# jetson_board.net
KiCad netlist of a schematic drawn in EAGLE
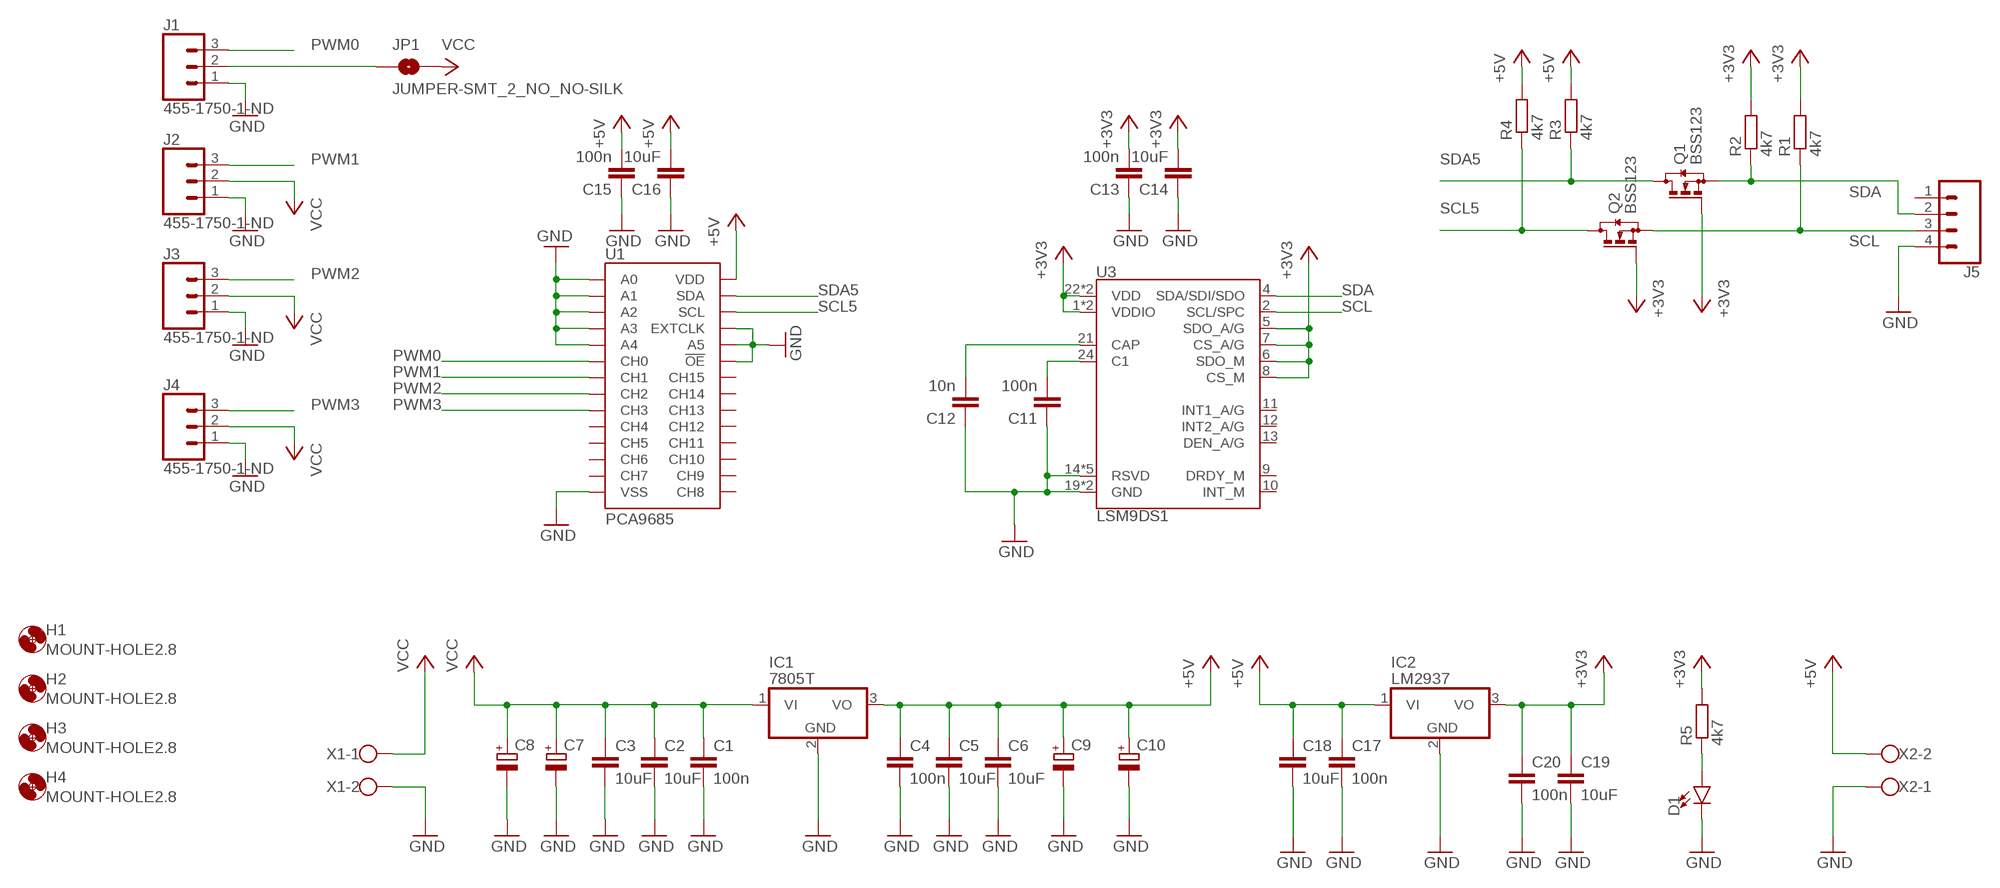
[diagram p0: schematic, sheet 1]

(export (version "E")
  (design (tool "Eeschema 10.0.6"))
  (components
    (comp (ref "C1")
      (value "100n")
      (footprint "eagle-import:C0805")
      (libsource (lib "eagle-import") (part "C-EUC0805"))
    )
    (comp (ref "C2")
      (value "10uF")
      (footprint "eagle-import:C0805")
      (libsource (lib "eagle-import") (part "C-EUC0805"))
    )
    (comp (ref "C3")
      (value "10uF")
      (footprint "eagle-import:C0805")
      (libsource (lib "eagle-import") (part "C-EUC0805"))
    )
    (comp (ref "C4")
      (value "100n")
      (footprint "eagle-import:C0805")
      (libsource (lib "eagle-import") (part "C-EUC0805"))
    )
    (comp (ref "C5")
      (value "10uF")
      (footprint "eagle-import:C0805")
      (libsource (lib "eagle-import") (part "C-EUC0805"))
    )
    (comp (ref "C6")
      (value "10uF")
      (footprint "eagle-import:C0805")
      (libsource (lib "eagle-import") (part "C-EUC0805"))
    )
    (comp (ref "C7")
      (value "CPOL-EUUD-8X10")
      (footprint "eagle-import:UD-8X10_NICHICON")
      (libsource (lib "eagle-import") (part "CPOL-EUUD-8X10"))
    )
    (comp (ref "C8")
      (value "CPOL-EUUD-8X10")
      (footprint "eagle-import:UD-8X10_NICHICON")
      (libsource (lib "eagle-import") (part "CPOL-EUUD-8X10"))
    )
    (comp (ref "C9")
      (value "CPOL-EUUD-8X10")
      (footprint "eagle-import:UD-8X10_NICHICON")
      (libsource (lib "eagle-import") (part "CPOL-EUUD-8X10"))
    )
    (comp (ref "C10")
      (value "CPOL-EUUD-8X10")
      (footprint "eagle-import:UD-8X10_NICHICON")
      (libsource (lib "eagle-import") (part "CPOL-EUUD-8X10"))
    )
    (comp (ref "C11")
      (value "100n")
      (footprint "eagle-import:C0805")
      (libsource (lib "eagle-import") (part "C-EUC0805"))
    )
    (comp (ref "C12")
      (value "10n")
      (footprint "eagle-import:C0805")
      (libsource (lib "eagle-import") (part "C-EUC0805"))
    )
    (comp (ref "C13")
      (value "100n")
      (footprint "eagle-import:C0805")
      (libsource (lib "eagle-import") (part "C-EUC0805"))
    )
    (comp (ref "C14")
      (value "10uF")
      (footprint "eagle-import:C0805")
      (libsource (lib "eagle-import") (part "C-EUC0805"))
    )
    (comp (ref "C15")
      (value "100n")
      (footprint "eagle-import:C0805")
      (libsource (lib "eagle-import") (part "C-EUC0805"))
    )
    (comp (ref "C16")
      (value "10uF")
      (footprint "eagle-import:C0805")
      (libsource (lib "eagle-import") (part "C-EUC0805"))
    )
    (comp (ref "C17")
      (value "100n")
      (footprint "eagle-import:C0805")
      (libsource (lib "eagle-import") (part "C-EUC0805"))
    )
    (comp (ref "C18")
      (value "10uF")
      (footprint "eagle-import:C0805")
      (libsource (lib "eagle-import") (part "C-EUC0805"))
    )
    (comp (ref "C19")
      (value "10uF")
      (footprint "eagle-import:C0805")
      (libsource (lib "eagle-import") (part "C-EUC0805"))
    )
    (comp (ref "C20")
      (value "100n")
      (footprint "eagle-import:C0805")
      (libsource (lib "eagle-import") (part "C-EUC0805"))
    )
    (comp (ref "D1")
      (value "LED1206")
      (footprint "eagle-import:LED-1206")
      (libsource (lib "eagle-import") (part "LED1206"))
    )
    (comp (ref "H1")
      (value "MOUNT-HOLE2.8")
      (footprint "eagle-import:2,8")
      (libsource (lib "eagle-import") (part "MOUNT-HOLE2.8"))
    )
    (comp (ref "H2")
      (value "MOUNT-HOLE2.8")
      (footprint "eagle-import:2,8")
      (libsource (lib "eagle-import") (part "MOUNT-HOLE2.8"))
    )
    (comp (ref "H3")
      (value "MOUNT-HOLE2.8")
      (footprint "eagle-import:2,8")
      (libsource (lib "eagle-import") (part "MOUNT-HOLE2.8"))
    )
    (comp (ref "H4")
      (value "MOUNT-HOLE2.8")
      (footprint "eagle-import:2,8")
      (libsource (lib "eagle-import") (part "MOUNT-HOLE2.8"))
    )
    (comp (ref "IC1")
      (value "7805T")
      (footprint "eagle-import:TO220H")
      (libsource (lib "eagle-import") (part "78T05"))
    )
    (comp (ref "IC2")
      (value "LM2937")
      (footprint "eagle-import:TO263-3")
      (libsource (lib "eagle-import") (part "LM2937"))
    )
    (comp (ref "J1")
      (value "455-1750-1-ND")
      (footprint "eagle-import:1X03")
      (libsource (lib "eagle-import") (part "CONN_03"))
    )
    (comp (ref "J2")
      (value "455-1750-1-ND")
      (footprint "eagle-import:1X03")
      (libsource (lib "eagle-import") (part "CONN_03"))
    )
    (comp (ref "J3")
      (value "455-1750-1-ND")
      (footprint "eagle-import:1X03")
      (libsource (lib "eagle-import") (part "CONN_03"))
    )
    (comp (ref "J4")
      (value "455-1750-1-ND")
      (footprint "eagle-import:1X03")
      (libsource (lib "eagle-import") (part "CONN_03"))
    )
    (comp (ref "J5")
      (value "CONN_04LONGPADS")
      (footprint "eagle-import:1X04_LONGPADS")
      (libsource (lib "eagle-import") (part "CONN_04LONGPADS"))
    )
    (comp (ref "JP1")
      (value "JUMPER-SMT_2_NO_NO-SILK")
      (footprint "eagle-import:SMT-JUMPER_2_NO_NO-SILK")
      (libsource (lib "eagle-import") (part "JUMPER-SMT_2_NO_NO-SILK"))
    )
    (comp (ref "Q1")
      (value "BSS123")
      (footprint "eagle-import:SOT23")
      (libsource (lib "eagle-import") (part "BSS123"))
    )
    (comp (ref "Q2")
      (value "BSS123")
      (footprint "eagle-import:SOT23")
      (libsource (lib "eagle-import") (part "BSS123"))
    )
    (comp (ref "R1")
      (value "4k7")
      (footprint "eagle-import:R0805")
      (libsource (lib "eagle-import") (part "R-EU_R0805"))
    )
    (comp (ref "R2")
      (value "4k7")
      (footprint "eagle-import:R0805")
      (libsource (lib "eagle-import") (part "R-EU_R0805"))
    )
    (comp (ref "R3")
      (value "4k7")
      (footprint "eagle-import:R0805")
      (libsource (lib "eagle-import") (part "R-EU_R0805"))
    )
    (comp (ref "R4")
      (value "4k7")
      (footprint "eagle-import:R0805")
      (libsource (lib "eagle-import") (part "R-EU_R0805"))
    )
    (comp (ref "R5")
      (value "4k7")
      (footprint "eagle-import:R0805")
      (libsource (lib "eagle-import") (part "R-EU_R0805"))
    )
    (comp (ref "U1")
      (value "PCA9685")
      (footprint "eagle-import:TSSOP-28_4MM")
      (libsource (lib "eagle-import") (part "PCA9685"))
    )
    (comp (ref "U3")
      (value "LSM9DS1")
      (footprint "eagle-import:LGA-24-3.5X3")
      (libsource (lib "eagle-import") (part "LSM9DS1"))
    )
    (comp (ref "X1")
      (value "W237-102")
      (footprint "eagle-import:W237-102")
      (fields (field (name "MPN") "237-102"))
      (libsource (lib "eagle-import") (part "W237-102"))
    )
    (comp (ref "X2")
      (value "W237-102")
      (footprint "eagle-import:W237-102")
      (fields (field (name "MPN") "237-102"))
      (libsource (lib "eagle-import") (part "W237-102"))
    )
  )
  (nets
    (net (code "1") (name "+3V3") (class "Default")
      (node (ref "C13") (pin "2") (pinfunction "2_2") (pintype "passive"))
      (node (ref "C14") (pin "2") (pinfunction "2_2") (pintype "passive"))
      (node (ref "C19") (pin "1") (pinfunction "1_1") (pintype "passive"))
      (node (ref "C20") (pin "1") (pinfunction "1_1") (pintype "passive"))
      (node (ref "IC2") (pin "3") (pinfunction "VO_3") (pintype "passive"))
      (node (ref "Q1") (pin "1") (pinfunction "G_1") (pintype "passive"))
      (node (ref "Q2") (pin "1") (pinfunction "G_1") (pintype "passive"))
      (node (ref "R1") (pin "2") (pinfunction "2_2") (pintype "passive"))
      (node (ref "R2") (pin "2") (pinfunction "2_2") (pintype "passive"))
      (node (ref "R5") (pin "2") (pinfunction "2_2") (pintype "passive"))
      (node (ref "U3") (pin "1") (pinfunction "VDDIO_1") (pintype "bidirectional"))
      (node (ref "U3") (pin "22") (pinfunction "VDD_22") (pintype "bidirectional"))
      (node (ref "U3") (pin "23") (pinfunction "VDD_23") (pintype "bidirectional"))
      (node (ref "U3") (pin "3") (pinfunction "VDDIO_3") (pintype "bidirectional"))
      (node (ref "U3") (pin "5") (pinfunction "SDO_A/G_5") (pintype "bidirectional"))
      (node (ref "U3") (pin "6") (pinfunction "SDO_M_6") (pintype "bidirectional"))
      (node (ref "U3") (pin "7") (pinfunction "CS_A/G_7") (pintype "bidirectional"))
      (node (ref "U3") (pin "8") (pinfunction "CS_M_8") (pintype "bidirectional"))
    )
    (net (code "2") (name "+5V") (class "Default")
      (node (ref "C10") (pin "+") (pinfunction "+_+") (pintype "passive"))
      (node (ref "C15") (pin "2") (pinfunction "2_2") (pintype "passive"))
      (node (ref "C16") (pin "2") (pinfunction "2_2") (pintype "passive"))
      (node (ref "C17") (pin "1") (pinfunction "1_1") (pintype "passive"))
      (node (ref "C18") (pin "1") (pinfunction "1_1") (pintype "passive"))
      (node (ref "C4") (pin "1") (pinfunction "1_1") (pintype "passive"))
      (node (ref "C5") (pin "1") (pinfunction "1_1") (pintype "passive"))
      (node (ref "C6") (pin "1") (pinfunction "1_1") (pintype "passive"))
      (node (ref "C9") (pin "+") (pinfunction "+_+") (pintype "passive"))
      (node (ref "IC1") (pin "3") (pinfunction "VO_3") (pintype "passive"))
      (node (ref "IC2") (pin "1") (pinfunction "VI_1") (pintype "input"))
      (node (ref "R3") (pin "2") (pinfunction "2_2") (pintype "passive"))
      (node (ref "R4") (pin "2") (pinfunction "2_2") (pintype "passive"))
      (node (ref "U1") (pin "28") (pinfunction "VDD_28") (pintype "bidirectional"))
      (node (ref "X2") (pin "2") (pinfunction "KL_2") (pintype "passive"))
    )
    (net (code "3") (name "/PWM0") (class "Default")
      (node (ref "J1") (pin "3") (pinfunction "3_3") (pintype "passive"))
      (node (ref "U1") (pin "6") (pinfunction "CH0_6") (pintype "bidirectional"))
    )
    (net (code "4") (name "/PWM1") (class "Default")
      (node (ref "J2") (pin "3") (pinfunction "3_3") (pintype "passive"))
      (node (ref "U1") (pin "7") (pinfunction "CH1_7") (pintype "bidirectional"))
    )
    (net (code "5") (name "/PWM2") (class "Default")
      (node (ref "J3") (pin "3") (pinfunction "3_3") (pintype "passive"))
      (node (ref "U1") (pin "8") (pinfunction "CH2_8") (pintype "bidirectional"))
    )
    (net (code "6") (name "/PWM3") (class "Default")
      (node (ref "J4") (pin "3") (pinfunction "3_3") (pintype "passive"))
      (node (ref "U1") (pin "9") (pinfunction "CH3_9") (pintype "bidirectional"))
    )
    (net (code "7") (name "/SCL") (class "Default")
      (node (ref "J5") (pin "3") (pinfunction "3_3") (pintype "passive"))
      (node (ref "Q2") (pin "2") (pinfunction "S_2") (pintype "passive"))
      (node (ref "R1") (pin "1") (pinfunction "1_1") (pintype "passive"))
      (node (ref "U3") (pin "2") (pinfunction "SCL/SPC_2") (pintype "bidirectional"))
    )
    (net (code "8") (name "/SCL5") (class "Default")
      (node (ref "Q2") (pin "3") (pinfunction "D_3") (pintype "passive"))
      (node (ref "R4") (pin "1") (pinfunction "1_1") (pintype "passive"))
      (node (ref "U1") (pin "26") (pinfunction "SCL_26") (pintype "bidirectional"))
    )
    (net (code "9") (name "/SDA") (class "Default")
      (node (ref "J5") (pin "2") (pinfunction "2_2") (pintype "passive"))
      (node (ref "Q1") (pin "2") (pinfunction "S_2") (pintype "passive"))
      (node (ref "R2") (pin "1") (pinfunction "1_1") (pintype "passive"))
      (node (ref "U3") (pin "4") (pinfunction "SDA/SDI/SDO_4") (pintype "bidirectional"))
    )
    (net (code "10") (name "/SDA5") (class "Default")
      (node (ref "Q1") (pin "3") (pinfunction "D_3") (pintype "passive"))
      (node (ref "R3") (pin "1") (pinfunction "1_1") (pintype "passive"))
      (node (ref "U1") (pin "27") (pinfunction "SDA_27") (pintype "bidirectional"))
    )
    (net (code "11") (name "GND") (class "Default")
      (node (ref "C1") (pin "2") (pinfunction "2_2") (pintype "passive"))
      (node (ref "C10") (pin "-") (pinfunction "-_-") (pintype "passive"))
      (node (ref "C11") (pin "1") (pinfunction "1_1") (pintype "passive"))
      (node (ref "C12") (pin "1") (pinfunction "1_1") (pintype "passive"))
      (node (ref "C13") (pin "1") (pinfunction "1_1") (pintype "passive"))
      (node (ref "C14") (pin "1") (pinfunction "1_1") (pintype "passive"))
      (node (ref "C15") (pin "1") (pinfunction "1_1") (pintype "passive"))
      (node (ref "C16") (pin "1") (pinfunction "1_1") (pintype "passive"))
      (node (ref "C17") (pin "2") (pinfunction "2_2") (pintype "passive"))
      (node (ref "C18") (pin "2") (pinfunction "2_2") (pintype "passive"))
      (node (ref "C19") (pin "2") (pinfunction "2_2") (pintype "passive"))
      (node (ref "C2") (pin "2") (pinfunction "2_2") (pintype "passive"))
      (node (ref "C20") (pin "2") (pinfunction "2_2") (pintype "passive"))
      (node (ref "C3") (pin "2") (pinfunction "2_2") (pintype "passive"))
      (node (ref "C4") (pin "2") (pinfunction "2_2") (pintype "passive"))
      (node (ref "C5") (pin "2") (pinfunction "2_2") (pintype "passive"))
      (node (ref "C6") (pin "2") (pinfunction "2_2") (pintype "passive"))
      (node (ref "C7") (pin "-") (pinfunction "-_-") (pintype "passive"))
      (node (ref "C8") (pin "-") (pinfunction "-_-") (pintype "passive"))
      (node (ref "C9") (pin "-") (pinfunction "-_-") (pintype "passive"))
      (node (ref "D1") (pin "C") (pinfunction "C_C") (pintype "passive"))
      (node (ref "IC1") (pin "2") (pinfunction "GND_2") (pintype "passive"))
      (node (ref "IC2") (pin "2") (pinfunction "GND_2") (pintype "passive"))
      (node (ref "J1") (pin "1") (pinfunction "1_1") (pintype "passive"))
      (node (ref "J2") (pin "1") (pinfunction "1_1") (pintype "passive"))
      (node (ref "J3") (pin "1") (pinfunction "1_1") (pintype "passive"))
      (node (ref "J4") (pin "1") (pinfunction "1_1") (pintype "passive"))
      (node (ref "J5") (pin "4") (pinfunction "4_4") (pintype "passive"))
      (node (ref "U1") (pin "1") (pinfunction "A0_1") (pintype "bidirectional"))
      (node (ref "U1") (pin "14") (pinfunction "VSS_14") (pintype "bidirectional"))
      (node (ref "U1") (pin "2") (pinfunction "A1_2") (pintype "bidirectional"))
      (node (ref "U1") (pin "23") (pinfunction "~{OE}_23") (pintype "bidirectional"))
      (node (ref "U1") (pin "24") (pinfunction "A5_24") (pintype "bidirectional"))
      (node (ref "U1") (pin "25") (pinfunction "EXTCLK_25") (pintype "bidirectional"))
      (node (ref "U1") (pin "3") (pinfunction "A2_3") (pintype "bidirectional"))
      (node (ref "U1") (pin "4") (pinfunction "A3_4") (pintype "bidirectional"))
      (node (ref "U1") (pin "5") (pinfunction "A4_5") (pintype "bidirectional"))
      (node (ref "U3") (pin "14") (pinfunction "RSVD_14") (pintype "bidirectional"))
      (node (ref "U3") (pin "15") (pinfunction "RSVD_15") (pintype "bidirectional"))
      (node (ref "U3") (pin "16") (pinfunction "RSVD_16") (pintype "bidirectional"))
      (node (ref "U3") (pin "17") (pinfunction "RSVD_17") (pintype "bidirectional"))
      (node (ref "U3") (pin "18") (pinfunction "RSVD_18") (pintype "bidirectional"))
      (node (ref "U3") (pin "19") (pinfunction "GND_19") (pintype "bidirectional"))
      (node (ref "U3") (pin "20") (pinfunction "GND_20") (pintype "bidirectional"))
      (node (ref "X1") (pin "2") (pinfunction "KL_2") (pintype "passive"))
      (node (ref "X2") (pin "1") (pinfunction "KL_1") (pintype "passive"))
    )
    (net (code "12") (name "Net-(D1-PadA)") (class "Default")
      (node (ref "D1") (pin "A") (pinfunction "A_A") (pintype "passive"))
      (node (ref "R5") (pin "1") (pinfunction "1_1") (pintype "passive"))
    )
    (net (code "13") (name "Net-(J1-Pad2)") (class "Default")
      (node (ref "J1") (pin "2") (pinfunction "2_2") (pintype "passive"))
      (node (ref "JP1") (pin "1") (pinfunction "1_1") (pintype "passive"))
    )
    (net (code "14") (name "Net-(U3-C1)") (class "Default")
      (node (ref "C11") (pin "2") (pinfunction "2_2") (pintype "passive"))
      (node (ref "U3") (pin "24") (pinfunction "C1_24") (pintype "bidirectional"))
    )
    (net (code "15") (name "Net-(U3-CAP)") (class "Default")
      (node (ref "C12") (pin "2") (pinfunction "2_2") (pintype "passive"))
      (node (ref "U3") (pin "21") (pinfunction "CAP_21") (pintype "bidirectional"))
    )
    (net (code "16") (name "VCC") (class "Default")
      (node (ref "C1") (pin "1") (pinfunction "1_1") (pintype "passive"))
      (node (ref "C2") (pin "1") (pinfunction "1_1") (pintype "passive"))
      (node (ref "C3") (pin "1") (pinfunction "1_1") (pintype "passive"))
      (node (ref "C7") (pin "+") (pinfunction "+_+") (pintype "passive"))
      (node (ref "C8") (pin "+") (pinfunction "+_+") (pintype "passive"))
      (node (ref "IC1") (pin "1") (pinfunction "VI_1") (pintype "input"))
      (node (ref "J2") (pin "2") (pinfunction "2_2") (pintype "passive"))
      (node (ref "J3") (pin "2") (pinfunction "2_2") (pintype "passive"))
      (node (ref "J4") (pin "2") (pinfunction "2_2") (pintype "passive"))
      (node (ref "JP1") (pin "2") (pinfunction "2_2") (pintype "passive"))
      (node (ref "X1") (pin "1") (pinfunction "KL_1") (pintype "passive"))
    )
    (net (code "17") (name "unconnected-(J5-Pad1)") (class "Default")
      (node (ref "J5") (pin "1") (pinfunction "1_1") (pintype "passive"))
    )
    (net (code "18") (name "unconnected-(U1-CH4-Pad10)") (class "Default")
      (node (ref "U1") (pin "10") (pinfunction "CH4_10") (pintype "bidirectional"))
    )
    (net (code "19") (name "unconnected-(U1-CH5-Pad11)") (class "Default")
      (node (ref "U1") (pin "11") (pinfunction "CH5_11") (pintype "bidirectional"))
    )
    (net (code "20") (name "unconnected-(U1-CH6-Pad12)") (class "Default")
      (node (ref "U1") (pin "12") (pinfunction "CH6_12") (pintype "bidirectional"))
    )
    (net (code "21") (name "unconnected-(U1-CH7-Pad13)") (class "Default")
      (node (ref "U1") (pin "13") (pinfunction "CH7_13") (pintype "bidirectional"))
    )
    (net (code "22") (name "unconnected-(U1-CH8-Pad15)") (class "Default")
      (node (ref "U1") (pin "15") (pinfunction "CH8_15") (pintype "bidirectional"))
    )
    (net (code "23") (name "unconnected-(U1-CH9-Pad16)") (class "Default")
      (node (ref "U1") (pin "16") (pinfunction "CH9_16") (pintype "bidirectional"))
    )
    (net (code "24") (name "unconnected-(U1-CH10-Pad17)") (class "Default")
      (node (ref "U1") (pin "17") (pinfunction "CH10_17") (pintype "bidirectional"))
    )
    (net (code "25") (name "unconnected-(U1-CH11-Pad18)") (class "Default")
      (node (ref "U1") (pin "18") (pinfunction "CH11_18") (pintype "bidirectional"))
    )
    (net (code "26") (name "unconnected-(U1-CH12-Pad19)") (class "Default")
      (node (ref "U1") (pin "19") (pinfunction "CH12_19") (pintype "bidirectional"))
    )
    (net (code "27") (name "unconnected-(U1-CH13-Pad20)") (class "Default")
      (node (ref "U1") (pin "20") (pinfunction "CH13_20") (pintype "bidirectional"))
    )
    (net (code "28") (name "unconnected-(U1-CH14-Pad21)") (class "Default")
      (node (ref "U1") (pin "21") (pinfunction "CH14_21") (pintype "bidirectional"))
    )
    (net (code "29") (name "unconnected-(U1-CH15-Pad22)") (class "Default")
      (node (ref "U1") (pin "22") (pinfunction "CH15_22") (pintype "bidirectional"))
    )
    (net (code "30") (name "unconnected-(U3-DEN_A{slash}G-Pad13)") (class "Default")
      (node (ref "U3") (pin "13") (pinfunction "DEN_A/G_13") (pintype "bidirectional"))
    )
    (net (code "31") (name "unconnected-(U3-DRDY_M-Pad9)") (class "Default")
      (node (ref "U3") (pin "9") (pinfunction "DRDY_M_9") (pintype "bidirectional"))
    )
    (net (code "32") (name "unconnected-(U3-INT1_A{slash}G-Pad11)") (class "Default")
      (node (ref "U3") (pin "11") (pinfunction "INT1_A/G_11") (pintype "bidirectional"))
    )
    (net (code "33") (name "unconnected-(U3-INT2_A{slash}G-Pad12)") (class "Default")
      (node (ref "U3") (pin "12") (pinfunction "INT2_A/G_12") (pintype "bidirectional"))
    )
    (net (code "34") (name "unconnected-(U3-INT_M-Pad10)") (class "Default")
      (node (ref "U3") (pin "10") (pinfunction "INT_M_10") (pintype "bidirectional"))
    )
  )
)
